# Sheet2.net
KiCad netlist of a schematic drawn in Altium Designer
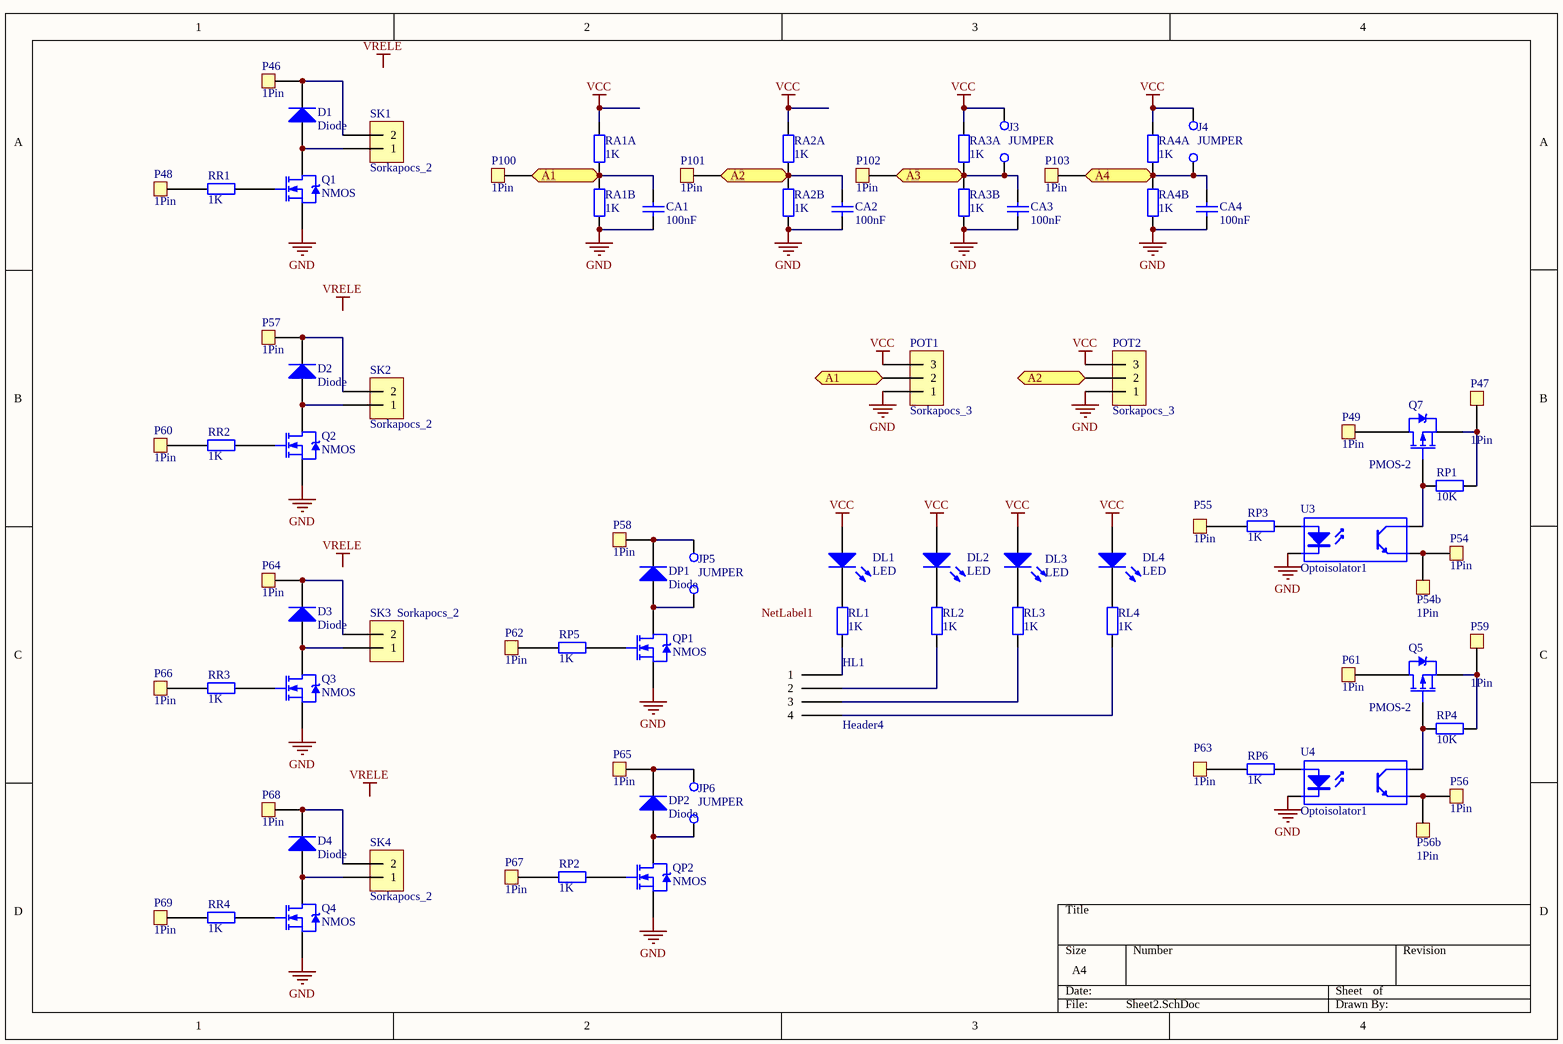
[diagram p0: Sheet2.SchDoc]

(export (version "E")
  (design (tool "Eeschema 10.0.6"))
  (components
    (comp (ref "CA1")
      (value "100nF")
      (footprint "FP_0805_CAP_085")
      (description "Capacitor")
      (libsource (lib "MySch") (part "CAP"))
    )
    (comp (ref "CA2")
      (value "100nF")
      (footprint "FP_0805_CAP_085")
      (description "Capacitor")
      (libsource (lib "MySch") (part "CAP"))
    )
    (comp (ref "CA3")
      (value "100nF")
      (footprint "FP_0805_CAP_085")
      (description "Capacitor")
      (libsource (lib "MySch") (part "CAP"))
    )
    (comp (ref "CA4")
      (value "100nF")
      (footprint "FP_0805_CAP_085")
      (description "Capacitor")
      (libsource (lib "MySch") (part "CAP"))
    )
    (comp (ref "D1")
      (value "Diode")
      (footprint "DO214")
      (fields (field (name "PUBLISHER") "Altium Limited"))
      (libsource (lib "MySch") (part "Diode"))
    )
    (comp (ref "D2")
      (value "Diode")
      (footprint "DO214")
      (fields (field (name "PUBLISHER") "Altium Limited"))
      (libsource (lib "MySch") (part "Diode"))
    )
    (comp (ref "D3")
      (value "Diode")
      (footprint "DO214")
      (fields (field (name "PUBLISHER") "Altium Limited"))
      (libsource (lib "MySch") (part "Diode"))
    )
    (comp (ref "D4")
      (value "Diode")
      (footprint "DO214")
      (fields (field (name "PUBLISHER") "Altium Limited"))
      (libsource (lib "MySch") (part "Diode"))
    )
    (comp (ref "DL1")
      (value "LED")
      (footprint "FP_0805_LED_RED")
      (description "Typical RED GaAs LED")
      (libsource (lib "MySch") (part "LED"))
    )
    (comp (ref "DL2")
      (value "LED")
      (footprint "FP_0805_LED_RED")
      (description "Typical RED GaAs LED")
      (libsource (lib "MySch") (part "LED"))
    )
    (comp (ref "DL3")
      (value "LED")
      (footprint "FP_0805_LED_RED")
      (description "Typical RED GaAs LED")
      (libsource (lib "MySch") (part "LED"))
    )
    (comp (ref "DL4")
      (value "LED")
      (footprint "FP_0805_LED_RED")
      (description "Typical RED GaAs LED")
      (libsource (lib "MySch") (part "LED"))
    )
    (comp (ref "DP1")
      (value "Diode")
      (footprint "DO214")
      (fields (field (name "PUBLISHER") "Altium Limited"))
      (libsource (lib "MySch") (part "Diode"))
    )
    (comp (ref "DP2")
      (value "Diode")
      (footprint "DO214")
      (fields (field (name "PUBLISHER") "Altium Limited"))
      (libsource (lib "MySch") (part "Diode"))
    )
    (comp (ref "HL1")
      (value "Header4")
      (footprint "FP_CONN4_TUSKE_254MM")
      (libsource (lib "MySch") (part "Header4"))
    )
    (comp (ref "J3")
      (value "JUMPER")
      (footprint "FP_CONN2_TUSKE_254MM")
      (description "Jumper Wire")
      (libsource (lib "MySch") (part "JUMPER"))
    )
    (comp (ref "J4")
      (value "JUMPER")
      (footprint "FP_CONN2_TUSKE_254MM")
      (description "Jumper Wire")
      (libsource (lib "MySch") (part "JUMPER"))
    )
    (comp (ref "JP5")
      (value "JUMPER")
      (footprint "FP_CONN2_TUSKE_254MM")
      (description "Jumper Wire")
      (libsource (lib "MySch") (part "JUMPER"))
    )
    (comp (ref "JP6")
      (value "JUMPER")
      (footprint "FP_CONN2_TUSKE_254MM")
      (description "Jumper Wire")
      (libsource (lib "MySch") (part "JUMPER"))
    )
    (comp (ref "P46") (value "1Pin") (footprint "Header1") (libsource (lib "MySch") (part "1Pin")))
    (comp (ref "P47") (value "1Pin") (footprint "Header1") (libsource (lib "") (part "1Pin_3")))
    (comp (ref "P48") (value "1Pin") (footprint "Header1") (libsource (lib "MySch") (part "1Pin")))
    (comp (ref "P49") (value "1Pin") (footprint "Header1") (libsource (lib "MySch") (part "1Pin")))
    (comp (ref "P54") (value "1Pin") (footprint "Header1") (libsource (lib "") (part "1Pin_2")))
    (comp (ref "P54b") (value "1Pin") (footprint "Header1") (libsource (lib "") (part "1Pin_1")))
    (comp (ref "P55") (value "1Pin") (footprint "Header1") (libsource (lib "MySch") (part "1Pin")))
    (comp (ref "P56") (value "1Pin") (footprint "Header1") (libsource (lib "") (part "1Pin_2")))
    (comp (ref "P56b") (value "1Pin") (footprint "Header1") (libsource (lib "") (part "1Pin_1")))
    (comp (ref "P57") (value "1Pin") (footprint "Header1") (libsource (lib "MySch") (part "1Pin")))
    (comp (ref "P58") (value "1Pin") (footprint "Header1") (libsource (lib "MySch") (part "1Pin")))
    (comp (ref "P59") (value "1Pin") (footprint "Header1") (libsource (lib "") (part "1Pin_3")))
    (comp (ref "P60") (value "1Pin") (footprint "Header1") (libsource (lib "MySch") (part "1Pin")))
    (comp (ref "P61") (value "1Pin") (footprint "Header1") (libsource (lib "MySch") (part "1Pin")))
    (comp (ref "P62") (value "1Pin") (footprint "Header1") (libsource (lib "MySch") (part "1Pin")))
    (comp (ref "P63") (value "1Pin") (footprint "Header1") (libsource (lib "MySch") (part "1Pin")))
    (comp (ref "P64") (value "1Pin") (footprint "Header1") (libsource (lib "MySch") (part "1Pin")))
    (comp (ref "P65") (value "1Pin") (footprint "Header1") (libsource (lib "MySch") (part "1Pin")))
    (comp (ref "P66") (value "1Pin") (footprint "Header1") (libsource (lib "MySch") (part "1Pin")))
    (comp (ref "P67") (value "1Pin") (footprint "Header1") (libsource (lib "MySch") (part "1Pin")))
    (comp (ref "P68") (value "1Pin") (footprint "Header1") (libsource (lib "MySch") (part "1Pin")))
    (comp (ref "P69") (value "1Pin") (footprint "Header1") (libsource (lib "MySch") (part "1Pin")))
    (comp (ref "P100") (value "1Pin") (footprint "Header1") (libsource (lib "MySch") (part "1Pin")))
    (comp (ref "P101") (value "1Pin") (footprint "Header1") (libsource (lib "MySch") (part "1Pin")))
    (comp (ref "P102") (value "1Pin") (footprint "Header1") (libsource (lib "MySch") (part "1Pin")))
    (comp (ref "P103") (value "1Pin") (footprint "Header1") (libsource (lib "MySch") (part "1Pin")))
    (comp (ref "POT1")
      (value "Sorkapocs_3")
      (footprint "SORKAPOCS_3")
      (libsource (lib "MySch") (part "Sorkapocs_3"))
    )
    (comp (ref "POT2")
      (value "Sorkapocs_3")
      (footprint "SORKAPOCS_3")
      (libsource (lib "MySch") (part "Sorkapocs_3"))
    )
    (comp (ref "Q1")
      (value "NMOS")
      (footprint "SOT95P245X110-3N")
      (description "N-Channel Power MOSFET")
      (fields (field (name "PUBLISHER") "Altium Limited"))
      (libsource (lib "MySch") (part "NMOS"))
    )
    (comp (ref "Q2")
      (value "NMOS")
      (footprint "SOT95P245X110-3N")
      (description "N-Channel Power MOSFET")
      (fields (field (name "PUBLISHER") "Altium Limited"))
      (libsource (lib "MySch") (part "NMOS"))
    )
    (comp (ref "Q3")
      (value "NMOS")
      (footprint "SOT95P245X110-3N")
      (description "N-Channel Power MOSFET")
      (fields (field (name "PUBLISHER") "Altium Limited"))
      (libsource (lib "MySch") (part "NMOS"))
    )
    (comp (ref "Q4")
      (value "NMOS")
      (footprint "SOT95P245X110-3N")
      (description "N-Channel Power MOSFET")
      (fields (field (name "PUBLISHER") "Altium Limited"))
      (libsource (lib "MySch") (part "NMOS"))
    )
    (comp (ref "Q5")
      (value "PMOS-2")
      (footprint "SOT95P245X110-3N")
      (description "P-Channel Power MOSFET")
      (fields (field (name "PUBLISHER") "Altium Limited"))
      (libsource (lib "MySch") (part "PMOS-2"))
    )
    (comp (ref "Q7")
      (value "PMOS-2")
      (footprint "SOT95P245X110-3N")
      (description "P-Channel Power MOSFET")
      (fields (field (name "PUBLISHER") "Altium Limited"))
      (libsource (lib "MySch") (part "PMOS-2"))
    )
    (comp (ref "QP1")
      (value "NMOS")
      (footprint "SOT95P245X110-3N")
      (description "N-Channel Power MOSFET")
      (fields (field (name "PUBLISHER") "Altium Limited"))
      (libsource (lib "MySch") (part "NMOS"))
    )
    (comp (ref "QP2")
      (value "NMOS")
      (footprint "SOT95P245X110-3N")
      (description "N-Channel Power MOSFET")
      (fields (field (name "PUBLISHER") "Altium Limited"))
      (libsource (lib "MySch") (part "NMOS"))
    )
    (comp (ref "RA1A")
      (value "1K")
      (footprint "0805")
      (description "Resistor")
      (fields (field (name "PUBLISHER") "Altium Limited"))
      (libsource (lib "MySch") (part "Resistor"))
    )
    (comp (ref "RA1B")
      (value "1K")
      (footprint "0805")
      (description "Resistor")
      (fields (field (name "PUBLISHER") "Altium Limited"))
      (libsource (lib "MySch") (part "Resistor"))
    )
    (comp (ref "RA2A")
      (value "1K")
      (footprint "0805")
      (description "Resistor")
      (fields (field (name "PUBLISHER") "Altium Limited"))
      (libsource (lib "MySch") (part "Resistor"))
    )
    (comp (ref "RA2B")
      (value "1K")
      (footprint "0805")
      (description "Resistor")
      (fields (field (name "PUBLISHER") "Altium Limited"))
      (libsource (lib "MySch") (part "Resistor"))
    )
    (comp (ref "RA3A")
      (value "1K")
      (footprint "0805")
      (description "Resistor")
      (fields (field (name "PUBLISHER") "Altium Limited"))
      (libsource (lib "MySch") (part "Resistor"))
    )
    (comp (ref "RA3B")
      (value "1K")
      (footprint "0805")
      (description "Resistor")
      (fields (field (name "PUBLISHER") "Altium Limited"))
      (libsource (lib "MySch") (part "Resistor"))
    )
    (comp (ref "RA4A")
      (value "1K")
      (footprint "0805")
      (description "Resistor")
      (fields (field (name "PUBLISHER") "Altium Limited"))
      (libsource (lib "MySch") (part "Resistor"))
    )
    (comp (ref "RA4B")
      (value "1K")
      (footprint "0805")
      (description "Resistor")
      (fields (field (name "PUBLISHER") "Altium Limited"))
      (libsource (lib "MySch") (part "Resistor"))
    )
    (comp (ref "RL1")
      (value "1K")
      (footprint "0805")
      (description "Resistor")
      (fields (field (name "PUBLISHER") "Altium Limited"))
      (libsource (lib "MySch") (part "Resistor"))
    )
    (comp (ref "RL2")
      (value "1K")
      (footprint "0805")
      (description "Resistor")
      (fields (field (name "PUBLISHER") "Altium Limited"))
      (libsource (lib "MySch") (part "Resistor"))
    )
    (comp (ref "RL3")
      (value "1K")
      (footprint "0805")
      (description "Resistor")
      (fields (field (name "PUBLISHER") "Altium Limited"))
      (libsource (lib "MySch") (part "Resistor"))
    )
    (comp (ref "RL4")
      (value "1K")
      (footprint "0805")
      (description "Resistor")
      (fields (field (name "PUBLISHER") "Altium Limited"))
      (libsource (lib "MySch") (part "Resistor"))
    )
    (comp (ref "RP1")
      (value "10K")
      (footprint "0805")
      (description "Resistor")
      (fields (field (name "PUBLISHER") "Altium Limited"))
      (libsource (lib "") (part "Resistor_1"))
    )
    (comp (ref "RP2")
      (value "1K")
      (footprint "0805")
      (description "Resistor")
      (fields (field (name "PUBLISHER") "Altium Limited"))
      (libsource (lib "") (part "Resistor_1"))
    )
    (comp (ref "RP3")
      (value "1K")
      (footprint "0805")
      (description "Resistor")
      (fields (field (name "PUBLISHER") "Altium Limited"))
      (libsource (lib "") (part "Resistor_1"))
    )
    (comp (ref "RP4")
      (value "10K")
      (footprint "0805")
      (description "Resistor")
      (fields (field (name "PUBLISHER") "Altium Limited"))
      (libsource (lib "") (part "Resistor_1"))
    )
    (comp (ref "RP5")
      (value "1K")
      (footprint "0805")
      (description "Resistor")
      (fields (field (name "PUBLISHER") "Altium Limited"))
      (libsource (lib "") (part "Resistor_1"))
    )
    (comp (ref "RP6")
      (value "1K")
      (footprint "0805")
      (description "Resistor")
      (fields (field (name "PUBLISHER") "Altium Limited"))
      (libsource (lib "") (part "Resistor_1"))
    )
    (comp (ref "RR1")
      (value "1K")
      (footprint "0805")
      (description "Resistor")
      (fields (field (name "PUBLISHER") "Altium Limited"))
      (libsource (lib "") (part "Resistor_1"))
    )
    (comp (ref "RR2")
      (value "1K")
      (footprint "0805")
      (description "Resistor")
      (fields (field (name "PUBLISHER") "Altium Limited"))
      (libsource (lib "") (part "Resistor_1"))
    )
    (comp (ref "RR3")
      (value "1K")
      (footprint "0805")
      (description "Resistor")
      (fields (field (name "PUBLISHER") "Altium Limited"))
      (libsource (lib "") (part "Resistor_1"))
    )
    (comp (ref "RR4")
      (value "1K")
      (footprint "0805")
      (description "Resistor")
      (fields (field (name "PUBLISHER") "Altium Limited"))
      (libsource (lib "") (part "Resistor_1"))
    )
    (comp (ref "SK1")
      (value "Sorkapocs_2")
      (footprint "SORKAPOCS_2")
      (libsource (lib "MySch") (part "Sorkapocs_2"))
    )
    (comp (ref "SK2")
      (value "Sorkapocs_2")
      (footprint "SORKAPOCS_2")
      (libsource (lib "MySch") (part "Sorkapocs_2"))
    )
    (comp (ref "SK3")
      (value "Sorkapocs_2")
      (footprint "SORKAPOCS_2")
      (libsource (lib "MySch") (part "Sorkapocs_2"))
    )
    (comp (ref "SK4")
      (value "Sorkapocs_2")
      (footprint "SORKAPOCS_2")
      (libsource (lib "MySch") (part "Sorkapocs_2"))
    )
    (comp (ref "U3")
      (value "Optoisolator1")
      (footprint "DIP-4")
      (description "4-Pin Phototransistor Optocoupler")
      (fields (field (name "PUBLISHER") "Altium Limited"))
      (libsource (lib "MySch") (part "Optoisolator1"))
    )
    (comp (ref "U4")
      (value "Optoisolator1")
      (footprint "DIP-4")
      (description "4-Pin Phototransistor Optocoupler")
      (fields (field (name "PUBLISHER") "Altium Limited"))
      (libsource (lib "MySch") (part "Optoisolator1"))
    )
  )
  (nets
    (net (code "1") (name "/A1") (class "Default")
      (node (ref "CA1") (pin "2") (pinfunction "2_2") (pintype "passive"))
      (node (ref "P100") (pin "1") (pinfunction "1_1") (pintype "passive"))
      (node (ref "POT1") (pin "2") (pinfunction "2_2") (pintype "passive"))
      (node (ref "RA1A") (pin "1") (pinfunction "1_1") (pintype "passive"))
      (node (ref "RA1B") (pin "2") (pinfunction "2_2") (pintype "passive"))
    )
    (net (code "2") (name "/A2") (class "Default")
      (node (ref "CA2") (pin "2") (pinfunction "2_2") (pintype "passive"))
      (node (ref "P101") (pin "1") (pinfunction "1_1") (pintype "passive"))
      (node (ref "POT2") (pin "2") (pinfunction "2_2") (pintype "passive"))
      (node (ref "RA2A") (pin "1") (pinfunction "1_1") (pintype "passive"))
      (node (ref "RA2B") (pin "2") (pinfunction "2_2") (pintype "passive"))
    )
    (net (code "3") (name "/A3") (class "Default")
      (node (ref "CA3") (pin "2") (pinfunction "2_2") (pintype "passive"))
      (node (ref "J3") (pin "1") (pinfunction "C1_1") (pintype "passive"))
      (node (ref "P102") (pin "1") (pinfunction "1_1") (pintype "passive"))
      (node (ref "RA3A") (pin "1") (pinfunction "1_1") (pintype "passive"))
      (node (ref "RA3B") (pin "2") (pinfunction "2_2") (pintype "passive"))
    )
    (net (code "4") (name "/A4") (class "Default")
      (node (ref "CA4") (pin "2") (pinfunction "2_2") (pintype "passive"))
      (node (ref "J4") (pin "1") (pinfunction "C1_1") (pintype "passive"))
      (node (ref "P103") (pin "1") (pinfunction "1_1") (pintype "passive"))
      (node (ref "RA4A") (pin "1") (pinfunction "1_1") (pintype "passive"))
      (node (ref "RA4B") (pin "2") (pinfunction "2_2") (pintype "passive"))
    )
    (net (code "6") (name "GND") (class "Default")
      (node (ref "CA1") (pin "1") (pinfunction "1_1") (pintype "passive"))
      (node (ref "CA2") (pin "1") (pinfunction "1_1") (pintype "passive"))
      (node (ref "CA3") (pin "1") (pinfunction "1_1") (pintype "passive"))
      (node (ref "CA4") (pin "1") (pinfunction "1_1") (pintype "passive"))
      (node (ref "POT1") (pin "1") (pinfunction "1_1") (pintype "passive"))
      (node (ref "POT2") (pin "1") (pinfunction "1_1") (pintype "passive"))
      (node (ref "Q1") (pin "S") (pinfunction "S_S") (pintype "passive"))
      (node (ref "Q2") (pin "S") (pinfunction "S_S") (pintype "passive"))
      (node (ref "Q3") (pin "S") (pinfunction "S_S") (pintype "passive"))
      (node (ref "Q4") (pin "S") (pinfunction "S_S") (pintype "passive"))
      (node (ref "QP1") (pin "S") (pinfunction "S_S") (pintype "passive"))
      (node (ref "QP2") (pin "S") (pinfunction "S_S") (pintype "passive"))
      (node (ref "RA1B") (pin "1") (pinfunction "1_1") (pintype "passive"))
      (node (ref "RA2B") (pin "1") (pinfunction "1_1") (pintype "passive"))
      (node (ref "RA3B") (pin "1") (pinfunction "1_1") (pintype "passive"))
      (node (ref "RA4B") (pin "1") (pinfunction "1_1") (pintype "passive"))
      (node (ref "U3") (pin "2") (pinfunction "K_2") (pintype "passive"))
      (node (ref "U4") (pin "2") (pinfunction "K_2") (pintype "passive"))
    )
    (net (code "7") (name "Net-(D1-A)") (class "Default")
      (node (ref "D1") (pin "1") (pinfunction "A_1") (pintype "passive"))
      (node (ref "Q1") (pin "D") (pinfunction "D_D") (pintype "passive"))
      (node (ref "SK1") (pin "1") (pinfunction "1_1") (pintype "passive"))
    )
    (net (code "8") (name "Net-(D1-K)") (class "Default")
      (node (ref "D1") (pin "2") (pinfunction "K_2") (pintype "passive"))
      (node (ref "P46") (pin "1") (pinfunction "1_1") (pintype "passive"))
      (node (ref "SK1") (pin "2") (pinfunction "2_2") (pintype "passive"))
    )
    (net (code "9") (name "Net-(D2-A)") (class "Default")
      (node (ref "D2") (pin "1") (pinfunction "A_1") (pintype "passive"))
      (node (ref "Q2") (pin "D") (pinfunction "D_D") (pintype "passive"))
      (node (ref "SK2") (pin "1") (pinfunction "1_1") (pintype "passive"))
    )
    (net (code "10") (name "Net-(D2-K)") (class "Default")
      (node (ref "D2") (pin "2") (pinfunction "K_2") (pintype "passive"))
      (node (ref "P57") (pin "1") (pinfunction "1_1") (pintype "passive"))
      (node (ref "SK2") (pin "2") (pinfunction "2_2") (pintype "passive"))
    )
    (net (code "11") (name "Net-(D3-A)") (class "Default")
      (node (ref "D3") (pin "1") (pinfunction "A_1") (pintype "passive"))
      (node (ref "Q3") (pin "D") (pinfunction "D_D") (pintype "passive"))
      (node (ref "SK3") (pin "1") (pinfunction "1_1") (pintype "passive"))
    )
    (net (code "12") (name "Net-(D3-K)") (class "Default")
      (node (ref "D3") (pin "2") (pinfunction "K_2") (pintype "passive"))
      (node (ref "P64") (pin "1") (pinfunction "1_1") (pintype "passive"))
      (node (ref "SK3") (pin "2") (pinfunction "2_2") (pintype "passive"))
    )
    (net (code "13") (name "Net-(D4-A)") (class "Default")
      (node (ref "D4") (pin "1") (pinfunction "A_1") (pintype "passive"))
      (node (ref "Q4") (pin "D") (pinfunction "D_D") (pintype "passive"))
      (node (ref "SK4") (pin "1") (pinfunction "1_1") (pintype "passive"))
    )
    (net (code "14") (name "Net-(D4-K)") (class "Default")
      (node (ref "D4") (pin "2") (pinfunction "K_2") (pintype "passive"))
      (node (ref "P68") (pin "1") (pinfunction "1_1") (pintype "passive"))
      (node (ref "SK4") (pin "2") (pinfunction "2_2") (pintype "passive"))
    )
    (net (code "15") (name "Net-(DL1-K)") (class "Default")
      (node (ref "DL1") (pin "2") (pinfunction "K_2") (pintype "passive"))
      (node (ref "RL1") (pin "2") (pinfunction "2_2") (pintype "passive"))
    )
    (net (code "16") (name "Net-(DL2-K)") (class "Default")
      (node (ref "DL2") (pin "2") (pinfunction "K_2") (pintype "passive"))
      (node (ref "RL2") (pin "2") (pinfunction "2_2") (pintype "passive"))
    )
    (net (code "17") (name "Net-(DL3-K)") (class "Default")
      (node (ref "DL3") (pin "2") (pinfunction "K_2") (pintype "passive"))
      (node (ref "RL3") (pin "2") (pinfunction "2_2") (pintype "passive"))
    )
    (net (code "18") (name "Net-(DL4-K)") (class "Default")
      (node (ref "DL4") (pin "2") (pinfunction "K_2") (pintype "passive"))
      (node (ref "RL4") (pin "2") (pinfunction "2_2") (pintype "passive"))
    )
    (net (code "19") (name "Net-(DP1-A)") (class "Default")
      (node (ref "DP1") (pin "1") (pinfunction "A_1") (pintype "passive"))
      (node (ref "JP5") (pin "1") (pinfunction "C1_1") (pintype "passive"))
      (node (ref "QP1") (pin "D") (pinfunction "D_D") (pintype "passive"))
    )
    (net (code "20") (name "Net-(DP1-K)") (class "Default")
      (node (ref "DP1") (pin "2") (pinfunction "K_2") (pintype "passive"))
      (node (ref "JP5") (pin "2") (pinfunction "C2_2") (pintype "passive"))
      (node (ref "P58") (pin "1") (pinfunction "1_1") (pintype "passive"))
    )
    (net (code "21") (name "Net-(DP2-A)") (class "Default")
      (node (ref "DP2") (pin "1") (pinfunction "A_1") (pintype "passive"))
      (node (ref "JP6") (pin "1") (pinfunction "C1_1") (pintype "passive"))
      (node (ref "QP2") (pin "D") (pinfunction "D_D") (pintype "passive"))
    )
    (net (code "22") (name "Net-(DP2-K)") (class "Default")
      (node (ref "DP2") (pin "2") (pinfunction "K_2") (pintype "passive"))
      (node (ref "JP6") (pin "2") (pinfunction "C2_2") (pintype "passive"))
      (node (ref "P65") (pin "1") (pinfunction "1_1") (pintype "passive"))
    )
    (net (code "23") (name "Net-(HL1-Pad1)") (class "Default")
      (node (ref "HL1") (pin "1") (pinfunction "1_1") (pintype "passive"))
      (node (ref "RL1") (pin "1") (pinfunction "1_1") (pintype "passive"))
    )
    (net (code "24") (name "Net-(HL1-Pad2)") (class "Default")
      (node (ref "HL1") (pin "2") (pinfunction "2_2") (pintype "passive"))
      (node (ref "RL2") (pin "1") (pinfunction "1_1") (pintype "passive"))
    )
    (net (code "25") (name "Net-(HL1-Pad3)") (class "Default")
      (node (ref "HL1") (pin "3") (pinfunction "3_3") (pintype "passive"))
      (node (ref "RL3") (pin "1") (pinfunction "1_1") (pintype "passive"))
    )
    (net (code "26") (name "Net-(HL1-Pad4)") (class "Default")
      (node (ref "HL1") (pin "4") (pinfunction "4_4") (pintype "passive"))
      (node (ref "RL4") (pin "1") (pinfunction "1_1") (pintype "passive"))
    )
    (net (code "27") (name "Net-(P47-Pad1)") (class "Default")
      (node (ref "P47") (pin "1") (pinfunction "1_1") (pintype "passive"))
      (node (ref "Q7") (pin "S") (pinfunction "S_S") (pintype "passive"))
      (node (ref "RP1") (pin "1") (pinfunction "1_1") (pintype "passive"))
    )
    (net (code "28") (name "Net-(P48-Pad1)") (class "Default")
      (node (ref "P48") (pin "1") (pinfunction "1_1") (pintype "passive"))
      (node (ref "RR1") (pin "2") (pinfunction "2_2") (pintype "passive"))
    )
    (net (code "29") (name "Net-(P49-Pad1)") (class "Default")
      (node (ref "P49") (pin "1") (pinfunction "1_1") (pintype "passive"))
      (node (ref "Q7") (pin "D") (pinfunction "D_D") (pintype "passive"))
    )
    (net (code "30") (name "Net-(P55-Pad1)") (class "Default")
      (node (ref "P55") (pin "1") (pinfunction "1_1") (pintype "passive"))
      (node (ref "RP3") (pin "2") (pinfunction "2_2") (pintype "passive"))
    )
    (net (code "31") (name "Net-(P59-Pad1)") (class "Default")
      (node (ref "P59") (pin "1") (pinfunction "1_1") (pintype "passive"))
      (node (ref "Q5") (pin "S") (pinfunction "S_S") (pintype "passive"))
      (node (ref "RP4") (pin "1") (pinfunction "1_1") (pintype "passive"))
    )
    (net (code "32") (name "Net-(P60-Pad1)") (class "Default")
      (node (ref "P60") (pin "1") (pinfunction "1_1") (pintype "passive"))
      (node (ref "RR2") (pin "2") (pinfunction "2_2") (pintype "passive"))
    )
    (net (code "33") (name "Net-(P61-Pad1)") (class "Default")
      (node (ref "P61") (pin "1") (pinfunction "1_1") (pintype "passive"))
      (node (ref "Q5") (pin "D") (pinfunction "D_D") (pintype "passive"))
    )
    (net (code "34") (name "Net-(P62-Pad1)") (class "Default")
      (node (ref "P62") (pin "1") (pinfunction "1_1") (pintype "passive"))
      (node (ref "RP5") (pin "2") (pinfunction "2_2") (pintype "passive"))
    )
    (net (code "35") (name "Net-(P63-Pad1)") (class "Default")
      (node (ref "P63") (pin "1") (pinfunction "1_1") (pintype "passive"))
      (node (ref "RP6") (pin "2") (pinfunction "2_2") (pintype "passive"))
    )
    (net (code "36") (name "Net-(P66-Pad1)") (class "Default")
      (node (ref "P66") (pin "1") (pinfunction "1_1") (pintype "passive"))
      (node (ref "RR3") (pin "2") (pinfunction "2_2") (pintype "passive"))
    )
    (net (code "37") (name "Net-(P67-Pad1)") (class "Default")
      (node (ref "P67") (pin "1") (pinfunction "1_1") (pintype "passive"))
      (node (ref "RP2") (pin "2") (pinfunction "2_2") (pintype "passive"))
    )
    (net (code "38") (name "Net-(P69-Pad1)") (class "Default")
      (node (ref "P69") (pin "1") (pinfunction "1_1") (pintype "passive"))
      (node (ref "RR4") (pin "2") (pinfunction "2_2") (pintype "passive"))
    )
    (net (code "39") (name "Net-(Q1-PadG)") (class "Default")
      (node (ref "Q1") (pin "G") (pinfunction "G_G") (pintype "passive"))
      (node (ref "RR1") (pin "1") (pinfunction "1_1") (pintype "passive"))
    )
    (net (code "40") (name "Net-(Q2-PadG)") (class "Default")
      (node (ref "Q2") (pin "G") (pinfunction "G_G") (pintype "passive"))
      (node (ref "RR2") (pin "1") (pinfunction "1_1") (pintype "passive"))
    )
    (net (code "41") (name "Net-(Q3-PadG)") (class "Default")
      (node (ref "Q3") (pin "G") (pinfunction "G_G") (pintype "passive"))
      (node (ref "RR3") (pin "1") (pinfunction "1_1") (pintype "passive"))
    )
    (net (code "42") (name "Net-(Q4-PadG)") (class "Default")
      (node (ref "Q4") (pin "G") (pinfunction "G_G") (pintype "passive"))
      (node (ref "RR4") (pin "1") (pinfunction "1_1") (pintype "passive"))
    )
    (net (code "43") (name "Net-(QP1-PadG)") (class "Default")
      (node (ref "QP1") (pin "G") (pinfunction "G_G") (pintype "passive"))
      (node (ref "RP5") (pin "1") (pinfunction "1_1") (pintype "passive"))
    )
    (net (code "44") (name "Net-(QP2-PadG)") (class "Default")
      (node (ref "QP2") (pin "G") (pinfunction "G_G") (pintype "passive"))
      (node (ref "RP2") (pin "1") (pinfunction "1_1") (pintype "passive"))
    )
    (net (code "45") (name "Net-(U3-A)") (class "Default")
      (node (ref "RP3") (pin "1") (pinfunction "1_1") (pintype "passive"))
      (node (ref "U3") (pin "1") (pinfunction "A_1") (pintype "passive"))
    )
    (net (code "46") (name "Net-(U3-C)") (class "Default")
      (node (ref "Q7") (pin "G") (pinfunction "G_G") (pintype "passive"))
      (node (ref "RP1") (pin "2") (pinfunction "2_2") (pintype "passive"))
      (node (ref "U3") (pin "4") (pinfunction "C_4") (pintype "passive"))
    )
    (net (code "47") (name "Net-(U3-E)") (class "Default")
      (node (ref "P54") (pin "1") (pinfunction "1_1") (pintype "passive"))
      (node (ref "P54b") (pin "1") (pinfunction "1_1") (pintype "passive"))
      (node (ref "U3") (pin "3") (pinfunction "E_3") (pintype "passive"))
    )
    (net (code "48") (name "Net-(U4-A)") (class "Default")
      (node (ref "RP6") (pin "1") (pinfunction "1_1") (pintype "passive"))
      (node (ref "U4") (pin "1") (pinfunction "A_1") (pintype "passive"))
    )
    (net (code "49") (name "Net-(U4-C)") (class "Default")
      (node (ref "Q5") (pin "G") (pinfunction "G_G") (pintype "passive"))
      (node (ref "RP4") (pin "2") (pinfunction "2_2") (pintype "passive"))
      (node (ref "U4") (pin "4") (pinfunction "C_4") (pintype "passive"))
    )
    (net (code "50") (name "Net-(U4-E)") (class "Default")
      (node (ref "P56") (pin "1") (pinfunction "1_1") (pintype "passive"))
      (node (ref "P56b") (pin "1") (pinfunction "1_1") (pintype "passive"))
      (node (ref "U4") (pin "3") (pinfunction "E_3") (pintype "passive"))
    )
    (net (code "51") (name "VCC") (class "Default")
      (node (ref "DL1") (pin "1") (pinfunction "A_1") (pintype "passive"))
      (node (ref "DL2") (pin "1") (pinfunction "A_1") (pintype "passive"))
      (node (ref "DL3") (pin "1") (pinfunction "A_1") (pintype "passive"))
      (node (ref "DL4") (pin "1") (pinfunction "A_1") (pintype "passive"))
      (node (ref "J3") (pin "2") (pinfunction "C2_2") (pintype "passive"))
      (node (ref "J4") (pin "2") (pinfunction "C2_2") (pintype "passive"))
      (node (ref "POT1") (pin "3") (pinfunction "3_3") (pintype "passive"))
      (node (ref "POT2") (pin "3") (pinfunction "3_3") (pintype "passive"))
      (node (ref "RA1A") (pin "2") (pinfunction "2_2") (pintype "passive"))
      (node (ref "RA2A") (pin "2") (pinfunction "2_2") (pintype "passive"))
      (node (ref "RA3A") (pin "2") (pinfunction "2_2") (pintype "passive"))
      (node (ref "RA4A") (pin "2") (pinfunction "2_2") (pintype "passive"))
    )
  )
)
